# LTC2400_test.net
KiCad netlist of a schematic drawn in EAGLE
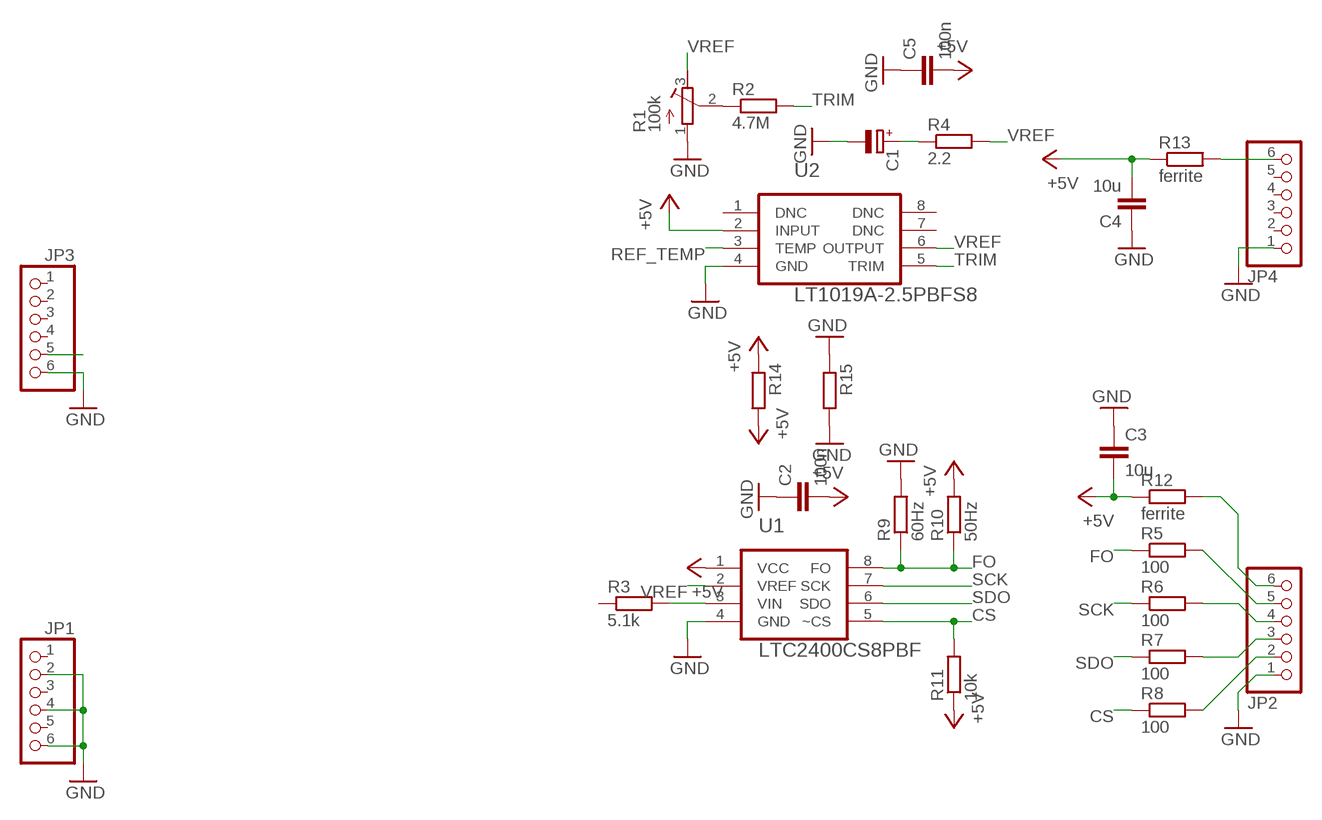
[diagram p0: schematic, sheet 1]

(export (version "E")
  (design (tool "Eeschema 10.0.6"))
  (components
    (comp (ref "C1")
      (value "CPOL-EUSMCB")
      (footprint "eagle-import:SMC_B")
      (libsource (lib "eagle-import") (part "CPOL-EUSMCB"))
    )
    (comp (ref "C2")
      (value "100n")
      (footprint "eagle-import:C0603")
      (libsource (lib "eagle-import") (part "C-EUC0603"))
    )
    (comp (ref "C3")
      (value "10u")
      (footprint "eagle-import:C0805")
      (libsource (lib "eagle-import") (part "C-EUC0805"))
    )
    (comp (ref "C4")
      (value "10u")
      (footprint "eagle-import:C0805")
      (libsource (lib "eagle-import") (part "C-EUC0805"))
    )
    (comp (ref "C5")
      (value "100n")
      (footprint "eagle-import:C0603")
      (libsource (lib "eagle-import") (part "C-EUC0603"))
    )
    (comp (ref "JP1")
      (value "PINHD-1X6SMALL")
      (footprint "eagle-import:1X06_SMALL")
      (libsource (lib "eagle-import") (part "PINHD-1X6SMALL"))
    )
    (comp (ref "JP2")
      (value "PINHD-1X6SMALL")
      (footprint "eagle-import:1X06_SMALL")
      (libsource (lib "eagle-import") (part "PINHD-1X6SMALL"))
    )
    (comp (ref "JP3")
      (value "PINHD-1X6SMALL")
      (footprint "eagle-import:1X06_SMALL")
      (libsource (lib "eagle-import") (part "PINHD-1X6SMALL"))
    )
    (comp (ref "JP4")
      (value "PINHD-1X6SMALL")
      (footprint "eagle-import:1X06_SMALL")
      (libsource (lib "eagle-import") (part "PINHD-1X6SMALL"))
    )
    (comp (ref "R1")
      (value "100k")
      (footprint "eagle-import:RTRIM3214W")
      (libsource (lib "eagle-import") (part "R-TRIMM3214W"))
    )
    (comp (ref "R2")
      (value "4.7M")
      (footprint "eagle-import:R0805")
      (libsource (lib "eagle-import") (part "R-EU_R0805"))
    )
    (comp (ref "R3")
      (value "5.1k")
      (footprint "eagle-import:R0805")
      (libsource (lib "eagle-import") (part "R-EU_R0805"))
    )
    (comp (ref "R4")
      (value "2.2")
      (footprint "eagle-import:R0805")
      (libsource (lib "eagle-import") (part "R-EU_R0805"))
    )
    (comp (ref "R5")
      (value "100")
      (footprint "eagle-import:R0603")
      (libsource (lib "eagle-import") (part "R-EU_R0603"))
    )
    (comp (ref "R6")
      (value "100")
      (footprint "eagle-import:R0603")
      (libsource (lib "eagle-import") (part "R-EU_R0603"))
    )
    (comp (ref "R7")
      (value "100")
      (footprint "eagle-import:R0603")
      (libsource (lib "eagle-import") (part "R-EU_R0603"))
    )
    (comp (ref "R8")
      (value "100")
      (footprint "eagle-import:R0603")
      (libsource (lib "eagle-import") (part "R-EU_R0603"))
    )
    (comp (ref "R9")
      (value "60Hz")
      (footprint "eagle-import:R0603")
      (libsource (lib "eagle-import") (part "R-EU_R0603"))
    )
    (comp (ref "R10")
      (value "50Hz")
      (footprint "eagle-import:R0603")
      (libsource (lib "eagle-import") (part "R-EU_R0603"))
    )
    (comp (ref "R11")
      (value "10k")
      (footprint "eagle-import:R0603")
      (libsource (lib "eagle-import") (part "R-EU_R0603"))
    )
    (comp (ref "R12")
      (value "ferrite")
      (footprint "eagle-import:R0805")
      (libsource (lib "eagle-import") (part "R-EU_R0805"))
    )
    (comp (ref "R13")
      (value "ferrite")
      (footprint "eagle-import:R0805")
      (libsource (lib "eagle-import") (part "R-EU_R0805"))
    )
    (comp (ref "R14")
      (value "R-EU_M1206")
      (footprint "eagle-import:M1206")
      (libsource (lib "eagle-import") (part "R-EU_M1206"))
    )
    (comp (ref "R15")
      (value "R-EU_M1206")
      (footprint "eagle-import:M1206")
      (libsource (lib "eagle-import") (part "R-EU_M1206"))
    )
    (comp (ref "U1")
      (value "LTC2400CS8PBF")
      (footprint "eagle-import:SOIC127P600X175-8N@1")
      (fields (field (name "MPN") "LTC2400CS8#PBF"))
      (libsource (lib "eagle-import") (part "LTC2400CS8PBF"))
    )
    (comp (ref "U2")
      (value "LT1019A-2.5PBFS8")
      (footprint "eagle-import:SOIC127P600X175-8N")
      (libsource (lib "eagle-import") (part "LT1019A-2.5PBFS8"))
    )
  )
  (nets
    (net (code "1") (name "+5V") (class "Default")
      (node (ref "C2") (pin "2") (pinfunction "2_2") (pintype "passive"))
      (node (ref "C3") (pin "2") (pinfunction "2_2") (pintype "passive"))
      (node (ref "C4") (pin "2") (pinfunction "2_2") (pintype "passive"))
      (node (ref "C5") (pin "2") (pinfunction "2_2") (pintype "passive"))
      (node (ref "R10") (pin "2") (pinfunction "2_2") (pintype "passive"))
      (node (ref "R11") (pin "1") (pinfunction "1_1") (pintype "passive"))
      (node (ref "R12") (pin "1") (pinfunction "1_1") (pintype "passive"))
      (node (ref "R13") (pin "1") (pinfunction "1_1") (pintype "passive"))
      (node (ref "R14") (pin "1") (pinfunction "1_1") (pintype "passive"))
      (node (ref "R14") (pin "2") (pinfunction "2_2") (pintype "passive"))
      (node (ref "U1") (pin "1") (pinfunction "VCC_1") (pintype "power_in"))
      (node (ref "U2") (pin "2") (pinfunction "INPUT_2") (pintype "input"))
    )
    (net (code "2") (name "/CS") (class "Default")
      (node (ref "R11") (pin "2") (pinfunction "2_2") (pintype "passive"))
      (node (ref "R8") (pin "1") (pinfunction "1_1") (pintype "passive"))
      (node (ref "U1") (pin "5") (pinfunction "~{CS}_5") (pintype "input"))
    )
    (net (code "3") (name "/FO") (class "Default")
      (node (ref "R10") (pin "1") (pinfunction "1_1") (pintype "passive"))
      (node (ref "R5") (pin "1") (pinfunction "1_1") (pintype "passive"))
      (node (ref "R9") (pin "1") (pinfunction "1_1") (pintype "passive"))
      (node (ref "U1") (pin "8") (pinfunction "FO_8") (pintype "input"))
    )
    (net (code "4") (name "/REF_TEMP") (class "Default")
      (node (ref "U2") (pin "3") (pinfunction "TEMP_3") (pintype "input"))
    )
    (net (code "5") (name "/SCK") (class "Default")
      (node (ref "R6") (pin "1") (pinfunction "1_1") (pintype "passive"))
      (node (ref "U1") (pin "7") (pinfunction "SCK_7") (pintype "input"))
    )
    (net (code "6") (name "/SDO") (class "Default")
      (node (ref "R7") (pin "1") (pinfunction "1_1") (pintype "passive"))
      (node (ref "U1") (pin "6") (pinfunction "SDO_6") (pintype "output"))
    )
    (net (code "7") (name "/TRIM") (class "Default")
      (node (ref "R2") (pin "2") (pinfunction "2_2") (pintype "passive"))
      (node (ref "U2") (pin "5") (pinfunction "TRIM_5") (pintype "input"))
    )
    (net (code "8") (name "/VREF") (class "Default")
      (node (ref "R1") (pin "3") (pinfunction "A_3") (pintype "passive"))
      (node (ref "R4") (pin "2") (pinfunction "2_2") (pintype "passive"))
      (node (ref "U1") (pin "2") (pinfunction "VREF_2") (pintype "input"))
      (node (ref "U2") (pin "6") (pinfunction "OUTPUT_6") (pintype "output"))
    )
    (net (code "9") (name "GND") (class "Default")
      (node (ref "C1") (pin "-") (pinfunction "-_-") (pintype "passive"))
      (node (ref "C2") (pin "1") (pinfunction "1_1") (pintype "passive"))
      (node (ref "C3") (pin "1") (pinfunction "1_1") (pintype "passive"))
      (node (ref "C4") (pin "1") (pinfunction "1_1") (pintype "passive"))
      (node (ref "C5") (pin "1") (pinfunction "1_1") (pintype "passive"))
      (node (ref "JP1") (pin "2") (pinfunction "2_2") (pintype "passive"))
      (node (ref "JP1") (pin "4") (pinfunction "4_4") (pintype "passive"))
      (node (ref "JP1") (pin "6") (pinfunction "6_6") (pintype "passive"))
      (node (ref "JP2") (pin "1") (pinfunction "1_1") (pintype "passive"))
      (node (ref "JP3") (pin "6") (pinfunction "6_6") (pintype "passive"))
      (node (ref "JP4") (pin "1") (pinfunction "1_1") (pintype "passive"))
      (node (ref "R1") (pin "1") (pinfunction "E_1") (pintype "passive"))
      (node (ref "R15") (pin "1") (pinfunction "1_1") (pintype "passive"))
      (node (ref "R15") (pin "2") (pinfunction "2_2") (pintype "passive"))
      (node (ref "R9") (pin "2") (pinfunction "2_2") (pintype "passive"))
      (node (ref "U1") (pin "4") (pinfunction "GND_4") (pintype "passive"))
      (node (ref "U2") (pin "4") (pinfunction "GND_4") (pintype "passive"))
    )
    (net (code "10") (name "Net-(C1-Pad+)") (class "Default")
      (node (ref "C1") (pin "+") (pinfunction "+_+") (pintype "passive"))
      (node (ref "R4") (pin "1") (pinfunction "1_1") (pintype "passive"))
    )
    (net (code "11") (name "Net-(JP2-Pad2)") (class "Default")
      (node (ref "JP2") (pin "2") (pinfunction "2_2") (pintype "passive"))
      (node (ref "R8") (pin "2") (pinfunction "2_2") (pintype "passive"))
    )
    (net (code "12") (name "Net-(JP2-Pad3)") (class "Default")
      (node (ref "JP2") (pin "3") (pinfunction "3_3") (pintype "passive"))
      (node (ref "R7") (pin "2") (pinfunction "2_2") (pintype "passive"))
    )
    (net (code "13") (name "Net-(JP2-Pad4)") (class "Default")
      (node (ref "JP2") (pin "4") (pinfunction "4_4") (pintype "passive"))
      (node (ref "R6") (pin "2") (pinfunction "2_2") (pintype "passive"))
    )
    (net (code "14") (name "Net-(JP2-Pad5)") (class "Default")
      (node (ref "JP2") (pin "5") (pinfunction "5_5") (pintype "passive"))
      (node (ref "R5") (pin "2") (pinfunction "2_2") (pintype "passive"))
    )
    (net (code "15") (name "Net-(JP2-Pad6)") (class "Default")
      (node (ref "JP2") (pin "6") (pinfunction "6_6") (pintype "passive"))
      (node (ref "R12") (pin "2") (pinfunction "2_2") (pintype "passive"))
    )
    (net (code "16") (name "Net-(JP4-Pad6)") (class "Default")
      (node (ref "JP4") (pin "6") (pinfunction "6_6") (pintype "passive"))
      (node (ref "R13") (pin "2") (pinfunction "2_2") (pintype "passive"))
    )
    (net (code "17") (name "Net-(R1-S)") (class "Default")
      (node (ref "R1") (pin "2") (pinfunction "S_2") (pintype "passive"))
      (node (ref "R2") (pin "1") (pinfunction "1_1") (pintype "passive"))
    )
    (net (code "18") (name "Net-(U1-VIN)") (class "Default")
      (node (ref "R3") (pin "2") (pinfunction "2_2") (pintype "passive"))
      (node (ref "U1") (pin "3") (pinfunction "VIN_3") (pintype "input"))
    )
    (net (code "19") (name "unconnected-(JP1-Pad1)") (class "Default")
      (node (ref "JP1") (pin "1") (pinfunction "1_1") (pintype "passive"))
    )
    (net (code "20") (name "unconnected-(JP1-Pad3)") (class "Default")
      (node (ref "JP1") (pin "3") (pinfunction "3_3") (pintype "passive"))
    )
    (net (code "21") (name "unconnected-(JP1-Pad5)") (class "Default")
      (node (ref "JP1") (pin "5") (pinfunction "5_5") (pintype "passive"))
    )
    (net (code "22") (name "unconnected-(JP3-Pad1)") (class "Default")
      (node (ref "JP3") (pin "1") (pinfunction "1_1") (pintype "passive"))
    )
    (net (code "23") (name "unconnected-(JP3-Pad2)") (class "Default")
      (node (ref "JP3") (pin "2") (pinfunction "2_2") (pintype "passive"))
    )
    (net (code "24") (name "unconnected-(JP3-Pad3)") (class "Default")
      (node (ref "JP3") (pin "3") (pinfunction "3_3") (pintype "passive"))
    )
    (net (code "25") (name "unconnected-(JP3-Pad4)") (class "Default")
      (node (ref "JP3") (pin "4") (pinfunction "4_4") (pintype "passive"))
    )
    (net (code "26") (name "unconnected-(JP3-Pad5)") (class "Default")
      (node (ref "JP3") (pin "5") (pinfunction "5_5") (pintype "passive"))
    )
    (net (code "27") (name "unconnected-(JP4-Pad2)") (class "Default")
      (node (ref "JP4") (pin "2") (pinfunction "2_2") (pintype "passive"))
    )
    (net (code "28") (name "unconnected-(JP4-Pad3)") (class "Default")
      (node (ref "JP4") (pin "3") (pinfunction "3_3") (pintype "passive"))
    )
    (net (code "29") (name "unconnected-(JP4-Pad4)") (class "Default")
      (node (ref "JP4") (pin "4") (pinfunction "4_4") (pintype "passive"))
    )
    (net (code "30") (name "unconnected-(JP4-Pad5)") (class "Default")
      (node (ref "JP4") (pin "5") (pinfunction "5_5") (pintype "passive"))
    )
    (net (code "31") (name "unconnected-(R3-Pad1)") (class "Default")
      (node (ref "R3") (pin "1") (pinfunction "1_1") (pintype "passive"))
    )
    (net (code "32") (name "unconnected-(U2-DNC-Pad1)") (class "Default")
      (node (ref "U2") (pin "1") (pinfunction "DNC_1") (pintype "no_connect"))
    )
    (net (code "33") (name "unconnected-(U2-DNC-Pad7)") (class "Default")
      (node (ref "U2") (pin "7") (pinfunction "DNC_7") (pintype "no_connect"))
    )
    (net (code "34") (name "unconnected-(U2-DNC-Pad8)") (class "Default")
      (node (ref "U2") (pin "8") (pinfunction "DNC_8") (pintype "no_connect"))
    )
  )
)
